# Access_System_Bmduino_V1_1.net
KiCad netlist of a schematic drawn in Altium Designer
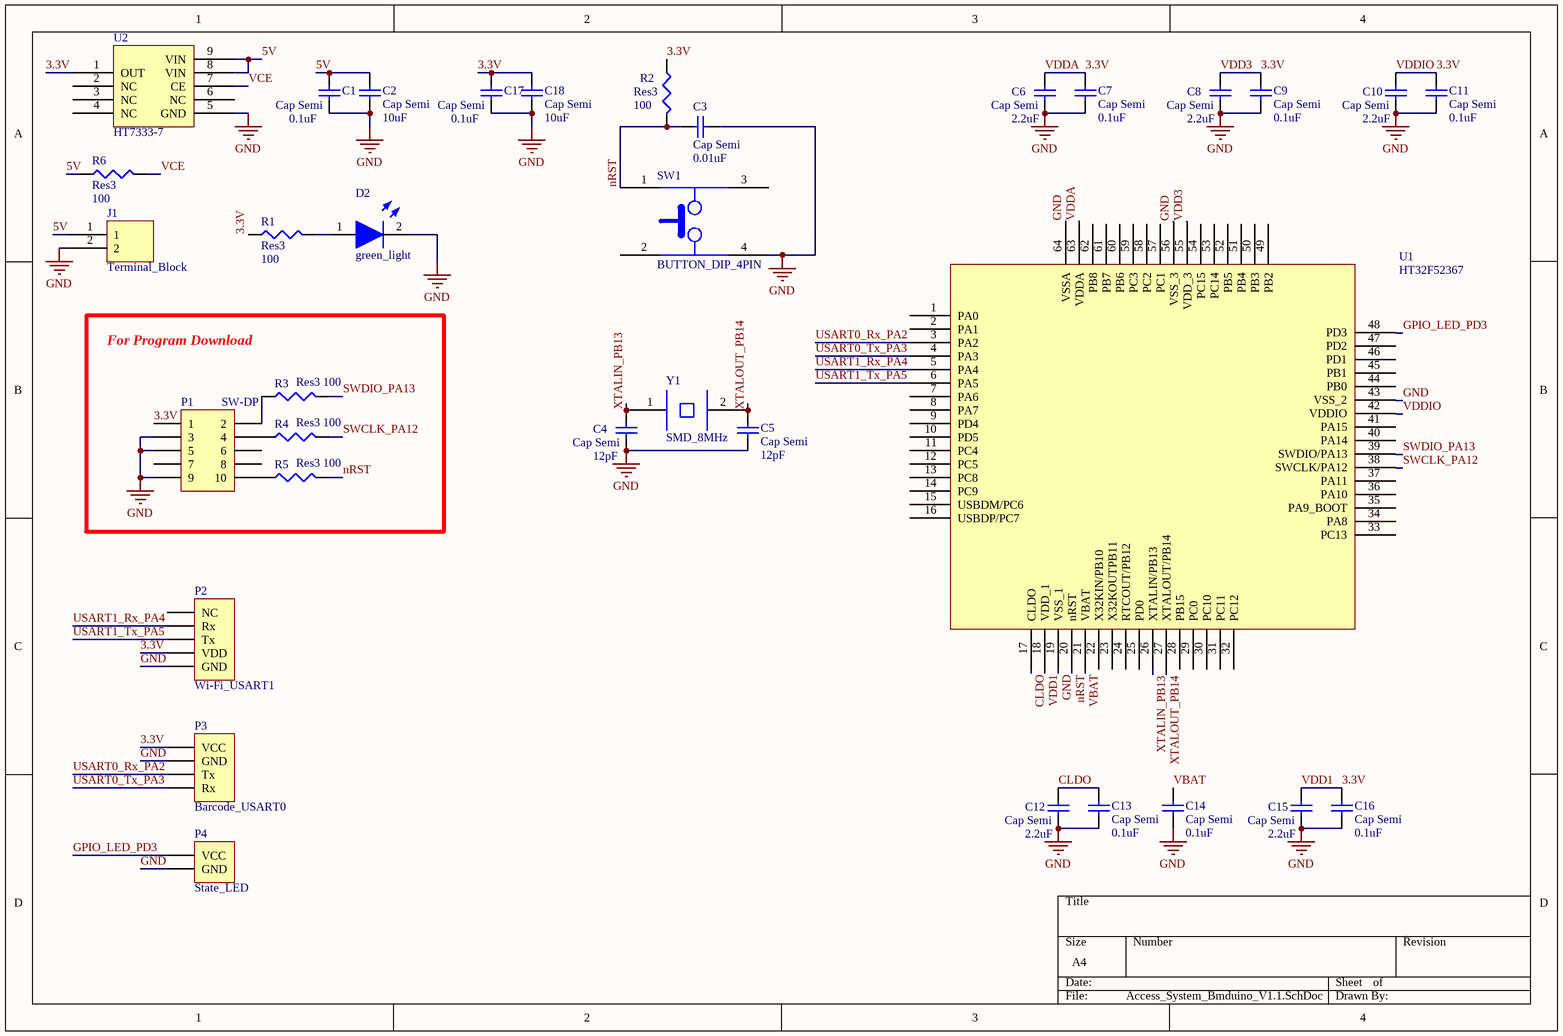
[diagram p0: Access_System_Bmduino_V1.1.SchDoc]

(export (version "E")
  (design (tool "Eeschema 10.0.6"))
  (components
    (comp (ref "C1")
      (value "Cap Semi")
      (footprint "1608[0603]")
      (description "Capacitor (Semiconductor SIM Model)")
      (fields (field (name "ALTIUM_VALUE") "0.1uF") (field (name "PUBLISHER") "Altium Limited"))
      (libsource (lib "Miscellaneous Devices") (part "Cap Semi"))
    )
    (comp (ref "C2")
      (value "Cap Semi")
      (footprint "1608[0603]")
      (description "Capacitor (Semiconductor SIM Model)")
      (fields (field (name "ALTIUM_VALUE") "10uF") (field (name "PUBLISHER") "Altium Limited"))
      (libsource (lib "Miscellaneous Devices") (part "Cap Semi"))
    )
    (comp (ref "C3")
      (value "Cap Semi")
      (footprint "1608[0603]")
      (description "Capacitor (Semiconductor SIM Model)")
      (fields (field (name "ALTIUM_VALUE") "0.01uF") (field (name "PUBLISHER") "Altium Limited"))
      (libsource (lib "Miscellaneous Devices") (part "Cap Semi"))
    )
    (comp (ref "C4")
      (value "Cap Semi")
      (footprint "1608[0603]")
      (description "Capacitor (Semiconductor SIM Model)")
      (fields (field (name "ALTIUM_VALUE") "12pF") (field (name "PUBLISHER") "Altium Limited"))
      (libsource (lib "Miscellaneous Devices") (part "Cap Semi"))
    )
    (comp (ref "C5")
      (value "Cap Semi")
      (footprint "1608[0603]")
      (description "Capacitor (Semiconductor SIM Model)")
      (fields (field (name "ALTIUM_VALUE") "12pF") (field (name "PUBLISHER") "Altium Limited"))
      (libsource (lib "Miscellaneous Devices") (part "Cap Semi"))
    )
    (comp (ref "C6")
      (value "Cap Semi")
      (footprint "1608[0603]")
      (description "Capacitor (Semiconductor SIM Model)")
      (fields (field (name "ALTIUM_VALUE") "2.2uF") (field (name "PUBLISHER") "Altium Limited"))
      (libsource (lib "Miscellaneous Devices") (part "Cap Semi"))
    )
    (comp (ref "C7")
      (value "Cap Semi")
      (footprint "1608[0603]")
      (description "Capacitor (Semiconductor SIM Model)")
      (fields (field (name "ALTIUM_VALUE") "0.1uF") (field (name "PUBLISHER") "Altium Limited"))
      (libsource (lib "Miscellaneous Devices") (part "Cap Semi"))
    )
    (comp (ref "C8")
      (value "Cap Semi")
      (footprint "1608[0603]")
      (description "Capacitor (Semiconductor SIM Model)")
      (fields (field (name "ALTIUM_VALUE") "2.2uF") (field (name "PUBLISHER") "Altium Limited"))
      (libsource (lib "Miscellaneous Devices") (part "Cap Semi"))
    )
    (comp (ref "C9")
      (value "Cap Semi")
      (footprint "1608[0603]")
      (description "Capacitor (Semiconductor SIM Model)")
      (fields (field (name "ALTIUM_VALUE") "0.1uF") (field (name "PUBLISHER") "Altium Limited"))
      (libsource (lib "Miscellaneous Devices") (part "Cap Semi"))
    )
    (comp (ref "C10")
      (value "Cap Semi")
      (footprint "1608[0603]")
      (description "Capacitor (Semiconductor SIM Model)")
      (fields (field (name "ALTIUM_VALUE") "2.2uF") (field (name "PUBLISHER") "Altium Limited"))
      (libsource (lib "Miscellaneous Devices") (part "Cap Semi"))
    )
    (comp (ref "C11")
      (value "Cap Semi")
      (footprint "1608[0603]")
      (description "Capacitor (Semiconductor SIM Model)")
      (fields (field (name "ALTIUM_VALUE") "0.1uF") (field (name "PUBLISHER") "Altium Limited"))
      (libsource (lib "Miscellaneous Devices") (part "Cap Semi"))
    )
    (comp (ref "C12")
      (value "Cap Semi")
      (footprint "1608[0603]")
      (description "Capacitor (Semiconductor SIM Model)")
      (fields (field (name "ALTIUM_VALUE") "2.2uF") (field (name "PUBLISHER") "Altium Limited"))
      (libsource (lib "Miscellaneous Devices") (part "Cap Semi"))
    )
    (comp (ref "C13")
      (value "Cap Semi")
      (footprint "1608[0603]")
      (description "Capacitor (Semiconductor SIM Model)")
      (fields (field (name "ALTIUM_VALUE") "0.1uF") (field (name "PUBLISHER") "Altium Limited"))
      (libsource (lib "Miscellaneous Devices") (part "Cap Semi"))
    )
    (comp (ref "C14")
      (value "Cap Semi")
      (footprint "1608[0603]")
      (description "Capacitor (Semiconductor SIM Model)")
      (fields (field (name "ALTIUM_VALUE") "0.1uF") (field (name "PUBLISHER") "Altium Limited"))
      (libsource (lib "Miscellaneous Devices") (part "Cap Semi"))
    )
    (comp (ref "C15")
      (value "Cap Semi")
      (footprint "1608[0603]")
      (description "Capacitor (Semiconductor SIM Model)")
      (fields (field (name "ALTIUM_VALUE") "2.2uF") (field (name "PUBLISHER") "Altium Limited"))
      (libsource (lib "Miscellaneous Devices") (part "Cap Semi"))
    )
    (comp (ref "C16")
      (value "Cap Semi")
      (footprint "1608[0603]")
      (description "Capacitor (Semiconductor SIM Model)")
      (fields (field (name "ALTIUM_VALUE") "0.1uF") (field (name "PUBLISHER") "Altium Limited"))
      (libsource (lib "Miscellaneous Devices") (part "Cap Semi"))
    )
    (comp (ref "C17")
      (value "Cap Semi")
      (footprint "1608[0603]")
      (description "Capacitor (Semiconductor SIM Model)")
      (fields (field (name "ALTIUM_VALUE") "0.1uF") (field (name "PUBLISHER") "Altium Limited"))
      (libsource (lib "Miscellaneous Devices") (part "Cap Semi"))
    )
    (comp (ref "C18")
      (value "Cap Semi")
      (footprint "1608[0603]")
      (description "Capacitor (Semiconductor SIM Model)")
      (fields (field (name "ALTIUM_VALUE") "10uF") (field (name "PUBLISHER") "Altium Limited"))
      (libsource (lib "Miscellaneous Devices") (part "Cap Semi"))
    )
    (comp (ref "D2")
      (value "green_light")
      (footprint "LED_Green")
      (libsource (lib "Lab_share") (part "LED_Green"))
    )
    (comp (ref "J1")
      (value "Terminal_Block")
      (footprint "terminal block")
      (libsource (lib "Lab_share") (part "Terminal Block"))
    )
    (comp (ref "P1")
      (value "SW-DP")
      (footprint "HDR2X5")
      (description "Header, 5-Pin, Dual row")
      (fields (field (name "PUBLISHER") "Altium Limited"))
      (libsource (lib "Miscellaneous Connectors") (part "Header 5X2"))
    )
    (comp (ref "P2")
      (value "Wi-Fi_USART1")
      (footprint "HDR1X5")
      (description "Header, 5-Pin")
      (fields (field (name "PUBLISHER") "Altium Limited"))
      (libsource (lib "Miscellaneous Connectors") (part "Header 5"))
    )
    (comp (ref "P3")
      (value "Barcode_USART0")
      (footprint "HDR1X4")
      (description "Header, 4-Pin")
      (fields (field (name "PUBLISHER") "Altium Limited"))
      (libsource (lib "Miscellaneous Connectors") (part "Header 4"))
    )
    (comp (ref "P4")
      (value "State_LED")
      (footprint "HDR1X2")
      (description "Header, 2-Pin")
      (fields (field (name "PUBLISHER") "Altium Limited"))
      (libsource (lib "Miscellaneous Connectors") (part "Header 2"))
    )
    (comp (ref "R1")
      (value "Res3")
      (footprint "J1-0603")
      (description "Resistor")
      (fields (field (name "ALTIUM_VALUE") "100") (field (name "PUBLISHER") "Altium Limited"))
      (libsource (lib "Miscellaneous Devices") (part "Res3"))
    )
    (comp (ref "R2")
      (value "Res3")
      (footprint "J1-0603")
      (description "Resistor")
      (fields (field (name "ALTIUM_VALUE") "100") (field (name "PUBLISHER") "Altium Limited"))
      (libsource (lib "Miscellaneous Devices") (part "Res3"))
    )
    (comp (ref "R3")
      (value "Res3")
      (footprint "J1-0603")
      (description "Resistor")
      (fields (field (name "ALTIUM_VALUE") "100") (field (name "PUBLISHER") "Altium Limited"))
      (libsource (lib "Miscellaneous Devices") (part "Res3"))
    )
    (comp (ref "R4")
      (value "Res3")
      (footprint "J1-0603")
      (description "Resistor")
      (fields (field (name "ALTIUM_VALUE") "100") (field (name "PUBLISHER") "Altium Limited"))
      (libsource (lib "Miscellaneous Devices") (part "Res3"))
    )
    (comp (ref "R5")
      (value "Res3")
      (footprint "J1-0603")
      (description "Resistor")
      (fields (field (name "ALTIUM_VALUE") "100") (field (name "PUBLISHER") "Altium Limited"))
      (libsource (lib "Miscellaneous Devices") (part "Res3"))
    )
    (comp (ref "R6")
      (value "Res3")
      (footprint "J1-0603")
      (description "Resistor")
      (fields (field (name "ALTIUM_VALUE") "100") (field (name "PUBLISHER") "Altium Limited"))
      (libsource (lib "Miscellaneous Devices") (part "Res3"))
    )
    (comp (ref "SW1")
      (value "BUTTON_DIP_4PIN")
      (footprint "Push_Button")
      (libsource (lib "Lab_share") (part "Push_Button"))
    )
    (comp (ref "U1")
      (value "HT32F52367")
      (footprint "HT32H52367")
      (libsource (lib "Lab_share") (part "HT32F52367"))
    )
    (comp (ref "U2") (value "HT7333-7") (footprint "HT7333") (libsource (lib "Lab_share") (part "HT7333")))
    (comp (ref "Y1")
      (value "SMD_8MHz")
      (footprint "Quartz-Crystal-8MHz")
      (libsource (lib "Lab_share") (part "Quartz_Crystal_8MHz"))
    )
  )
  (nets
    (net (code "1") (name "/3.3V") (class "Default")
      (node (ref "C10") (pin "1") (pinfunction "1_1") (pintype "passive"))
      (node (ref "C11") (pin "2") (pinfunction "2_2") (pintype "passive"))
      (node (ref "C15") (pin "1") (pinfunction "1_1") (pintype "passive"))
      (node (ref "C16") (pin "2") (pinfunction "2_2") (pintype "passive"))
      (node (ref "C17") (pin "2") (pinfunction "2_2") (pintype "passive"))
      (node (ref "C18") (pin "2") (pinfunction "2_2") (pintype "passive"))
      (node (ref "C6") (pin "1") (pinfunction "1_1") (pintype "passive"))
      (node (ref "C7") (pin "2") (pinfunction "2_2") (pintype "passive"))
      (node (ref "C8") (pin "1") (pinfunction "1_1") (pintype "passive"))
      (node (ref "C9") (pin "2") (pinfunction "2_2") (pintype "passive"))
      (node (ref "P1") (pin "1") (pinfunction "1_1") (pintype "passive"))
      (node (ref "P2") (pin "4") (pinfunction "VDD_4") (pintype "passive"))
      (node (ref "P3") (pin "1") (pinfunction "VCC_1") (pintype "passive"))
      (node (ref "R1") (pin "1") (pinfunction "1_1") (pintype "passive"))
      (node (ref "R2") (pin "1") (pinfunction "1_1") (pintype "passive"))
      (node (ref "U1") (pin "18") (pinfunction "VDD_1_18") (pintype "passive"))
      (node (ref "U1") (pin "42") (pinfunction "VDDIO_42") (pintype "passive"))
      (node (ref "U1") (pin "55") (pinfunction "VDD_3_55") (pintype "passive"))
      (node (ref "U1") (pin "63") (pinfunction "VDDA_63") (pintype "passive"))
      (node (ref "U2") (pin "1") (pinfunction "OUT_1") (pintype "passive"))
    )
    (net (code "2") (name "/5V") (class "Default")
      (node (ref "C1") (pin "2") (pinfunction "2_2") (pintype "passive"))
      (node (ref "C2") (pin "2") (pinfunction "2_2") (pintype "passive"))
      (node (ref "J1") (pin "1") (pinfunction "1_1") (pintype "passive"))
      (node (ref "R6") (pin "1") (pinfunction "1_1") (pintype "passive"))
      (node (ref "U2") (pin "8") (pinfunction "VIN_8") (pintype "passive"))
      (node (ref "U2") (pin "9") (pinfunction "VIN_9") (pintype "passive"))
    )
    (net (code "3") (name "/CLDO") (class "Default")
      (node (ref "C12") (pin "1") (pinfunction "1_1") (pintype "passive"))
      (node (ref "C13") (pin "2") (pinfunction "2_2") (pintype "passive"))
      (node (ref "U1") (pin "17") (pinfunction "CLDO_17") (pintype "passive"))
    )
    (net (code "4") (name "/GPIO_LED_PD3") (class "Default")
      (node (ref "P4") (pin "1") (pinfunction "VCC_1") (pintype "passive"))
      (node (ref "U1") (pin "48") (pinfunction "PD3_48") (pintype "passive"))
    )
    (net (code "5") (name "/SWCLK_PA12") (class "Default")
      (node (ref "R4") (pin "2") (pinfunction "2_2") (pintype "passive"))
      (node (ref "U1") (pin "38") (pinfunction "SWCLK/PA12_38") (pintype "passive"))
    )
    (net (code "6") (name "/SWDIO_PA13") (class "Default")
      (node (ref "R3") (pin "2") (pinfunction "2_2") (pintype "passive"))
      (node (ref "U1") (pin "39") (pinfunction "SWDIO/PA13_39") (pintype "passive"))
    )
    (net (code "7") (name "/USART0_Rx_PA2") (class "Default")
      (node (ref "P3") (pin "3") (pinfunction "Tx_3") (pintype "passive"))
      (node (ref "U1") (pin "3") (pinfunction "PA2_3") (pintype "passive"))
    )
    (net (code "8") (name "/USART0_Tx_PA3") (class "Default")
      (node (ref "P3") (pin "4") (pinfunction "Rx_4") (pintype "passive"))
      (node (ref "U1") (pin "4") (pinfunction "PA3_4") (pintype "passive"))
    )
    (net (code "9") (name "/USART1_Rx_PA4") (class "Default")
      (node (ref "P2") (pin "2") (pinfunction "Rx_2") (pintype "passive"))
      (node (ref "U1") (pin "5") (pinfunction "PA4_5") (pintype "passive"))
    )
    (net (code "10") (name "/USART1_Tx_PA5") (class "Default")
      (node (ref "P2") (pin "3") (pinfunction "Tx_3") (pintype "passive"))
      (node (ref "U1") (pin "6") (pinfunction "PA5_6") (pintype "passive"))
    )
    (net (code "11") (name "/VBAT") (class "Default")
      (node (ref "C14") (pin "2") (pinfunction "2_2") (pintype "passive"))
      (node (ref "U1") (pin "21") (pinfunction "VBAT_21") (pintype "passive"))
    )
    (net (code "12") (name "/VCE") (class "Default")
      (node (ref "R6") (pin "2") (pinfunction "2_2") (pintype "passive"))
      (node (ref "U2") (pin "7") (pinfunction "CE_7") (pintype "passive"))
    )
    (net (code "13") (name "/XTALIN_PB13") (class "Default")
      (node (ref "C4") (pin "1") (pinfunction "1_1") (pintype "passive"))
      (node (ref "U1") (pin "26") (pinfunction "XTALIN/PB13_26") (pintype "passive"))
      (node (ref "Y1") (pin "1") (pintype "passive"))
    )
    (net (code "14") (name "/XTALOUT_PB14") (class "Default")
      (node (ref "C5") (pin "2") (pinfunction "2_2") (pintype "passive"))
      (node (ref "U1") (pin "27") (pinfunction "XTALOUT/PB14_27") (pintype "passive"))
      (node (ref "Y1") (pin "2") (pintype "passive"))
    )
    (net (code "15") (name "/nRST") (class "Default")
      (node (ref "C3") (pin "2") (pinfunction "2_2") (pintype "passive"))
      (node (ref "R2") (pin "2") (pinfunction "2_2") (pintype "passive"))
      (node (ref "R5") (pin "2") (pinfunction "2_2") (pintype "passive"))
      (node (ref "SW1") (pin "1") (pintype "passive"))
      (node (ref "U1") (pin "20") (pinfunction "nRST_20") (pintype "passive"))
    )
    (net (code "16") (name "GND") (class "Default")
      (node (ref "C1") (pin "1") (pinfunction "1_1") (pintype "passive"))
      (node (ref "C10") (pin "2") (pinfunction "2_2") (pintype "passive"))
      (node (ref "C11") (pin "1") (pinfunction "1_1") (pintype "passive"))
      (node (ref "C12") (pin "2") (pinfunction "2_2") (pintype "passive"))
      (node (ref "C13") (pin "1") (pinfunction "1_1") (pintype "passive"))
      (node (ref "C14") (pin "1") (pinfunction "1_1") (pintype "passive"))
      (node (ref "C15") (pin "2") (pinfunction "2_2") (pintype "passive"))
      (node (ref "C16") (pin "1") (pinfunction "1_1") (pintype "passive"))
      (node (ref "C17") (pin "1") (pinfunction "1_1") (pintype "passive"))
      (node (ref "C18") (pin "1") (pinfunction "1_1") (pintype "passive"))
      (node (ref "C2") (pin "1") (pinfunction "1_1") (pintype "passive"))
      (node (ref "C3") (pin "1") (pinfunction "1_1") (pintype "passive"))
      (node (ref "C4") (pin "2") (pinfunction "2_2") (pintype "passive"))
      (node (ref "C5") (pin "1") (pinfunction "1_1") (pintype "passive"))
      (node (ref "C6") (pin "2") (pinfunction "2_2") (pintype "passive"))
      (node (ref "C7") (pin "1") (pinfunction "1_1") (pintype "passive"))
      (node (ref "C8") (pin "2") (pinfunction "2_2") (pintype "passive"))
      (node (ref "C9") (pin "1") (pinfunction "1_1") (pintype "passive"))
      (node (ref "D2") (pin "2") (pintype "passive"))
      (node (ref "J1") (pin "2") (pinfunction "2_2") (pintype "passive"))
      (node (ref "P1") (pin "3") (pinfunction "3_3") (pintype "passive"))
      (node (ref "P1") (pin "5") (pinfunction "5_5") (pintype "passive"))
      (node (ref "P1") (pin "9") (pinfunction "9_9") (pintype "passive"))
      (node (ref "P2") (pin "5") (pinfunction "GND_5") (pintype "passive"))
      (node (ref "P3") (pin "2") (pinfunction "GND_2") (pintype "passive"))
      (node (ref "P4") (pin "2") (pinfunction "GND_2") (pintype "passive"))
      (node (ref "SW1") (pin "4") (pintype "passive"))
      (node (ref "U1") (pin "19") (pinfunction "VSS_1_19") (pintype "passive"))
      (node (ref "U1") (pin "43") (pinfunction "VSS_2_43") (pintype "passive"))
      (node (ref "U1") (pin "56") (pinfunction "VSS_3_56") (pintype "passive"))
      (node (ref "U1") (pin "64") (pinfunction "VSSA_64") (pintype "passive"))
      (node (ref "U2") (pin "5") (pinfunction "GND_5") (pintype "passive"))
    )
    (net (code "17") (name "Net-(D2-Pad1)") (class "Default")
      (node (ref "D2") (pin "1") (pintype "passive"))
      (node (ref "R1") (pin "2") (pinfunction "2_2") (pintype "passive"))
    )
    (net (code "18") (name "Net-(P1-Pad2)") (class "Default")
      (node (ref "P1") (pin "2") (pinfunction "2_2") (pintype "passive"))
      (node (ref "R3") (pin "1") (pinfunction "1_1") (pintype "passive"))
    )
    (net (code "19") (name "Net-(P1-Pad4)") (class "Default")
      (node (ref "P1") (pin "4") (pinfunction "4_4") (pintype "passive"))
      (node (ref "R4") (pin "1") (pinfunction "1_1") (pintype "passive"))
    )
    (net (code "20") (name "Net-(P1-Pad10)") (class "Default")
      (node (ref "P1") (pin "10") (pinfunction "10_10") (pintype "passive"))
      (node (ref "R5") (pin "1") (pinfunction "1_1") (pintype "passive"))
    )
    (net (code "21") (name "unconnected-(P1-Pad6)") (class "Default")
      (node (ref "P1") (pin "6") (pinfunction "6_6") (pintype "passive"))
    )
    (net (code "22") (name "unconnected-(P1-Pad7)") (class "Default")
      (node (ref "P1") (pin "7") (pinfunction "7_7") (pintype "passive"))
    )
    (net (code "23") (name "unconnected-(P1-Pad8)") (class "Default")
      (node (ref "P1") (pin "8") (pinfunction "8_8") (pintype "passive"))
    )
    (net (code "24") (name "unconnected-(P2-NC-Pad1)") (class "Default")
      (node (ref "P2") (pin "1") (pinfunction "NC_1") (pintype "passive"))
    )
    (net (code "25") (name "unconnected-(SW1-Pad2)") (class "Default")
      (node (ref "SW1") (pin "2") (pintype "passive"))
    )
    (net (code "26") (name "unconnected-(SW1-Pad3)") (class "Default")
      (node (ref "SW1") (pin "3") (pintype "passive"))
    )
    (net (code "27") (name "unconnected-(U1-PA0-Pad1)") (class "Default")
      (node (ref "U1") (pin "1") (pinfunction "PA0_1") (pintype "passive"))
    )
    (net (code "28") (name "unconnected-(U1-PA1-Pad2)") (class "Default")
      (node (ref "U1") (pin "2") (pinfunction "PA1_2") (pintype "passive"))
    )
    (net (code "29") (name "unconnected-(U1-PA6-Pad7)") (class "Default")
      (node (ref "U1") (pin "7") (pinfunction "PA6_7") (pintype "passive"))
    )
    (net (code "30") (name "unconnected-(U1-PA7-Pad8)") (class "Default")
      (node (ref "U1") (pin "8") (pinfunction "PA7_8") (pintype "passive"))
    )
    (net (code "31") (name "unconnected-(U1-PA8-Pad34)") (class "Default")
      (node (ref "U1") (pin "34") (pinfunction "PA8_34") (pintype "passive"))
    )
    (net (code "32") (name "unconnected-(U1-PA9_BOOT-Pad35)") (class "Default")
      (node (ref "U1") (pin "35") (pinfunction "PA9_BOOT_35") (pintype "passive"))
    )
    (net (code "33") (name "unconnected-(U1-PA10-Pad36)") (class "Default")
      (node (ref "U1") (pin "36") (pinfunction "PA10_36") (pintype "passive"))
    )
    (net (code "34") (name "unconnected-(U1-PA11-Pad37)") (class "Default")
      (node (ref "U1") (pin "37") (pinfunction "PA11_37") (pintype "passive"))
    )
    (net (code "35") (name "unconnected-(U1-PA14-Pad40)") (class "Default")
      (node (ref "U1") (pin "40") (pinfunction "PA14_40") (pintype "passive"))
    )
    (net (code "36") (name "unconnected-(U1-PA15-Pad41)") (class "Default")
      (node (ref "U1") (pin "41") (pinfunction "PA15_41") (pintype "passive"))
    )
    (net (code "37") (name "unconnected-(U1-PB0-Pad44)") (class "Default")
      (node (ref "U1") (pin "44") (pinfunction "PB0_44") (pintype "passive"))
    )
    (net (code "38") (name "unconnected-(U1-PB1-Pad45)") (class "Default")
      (node (ref "U1") (pin "45") (pinfunction "PB1_45") (pintype "passive"))
    )
    (net (code "39") (name "unconnected-(U1-PB2-Pad49)") (class "Default")
      (node (ref "U1") (pin "49") (pinfunction "PB2_49") (pintype "passive"))
    )
    (net (code "40") (name "unconnected-(U1-PB3-Pad50)") (class "Default")
      (node (ref "U1") (pin "50") (pinfunction "PB3_50") (pintype "passive"))
    )
    (net (code "41") (name "unconnected-(U1-PB4-Pad51)") (class "Default")
      (node (ref "U1") (pin "51") (pinfunction "PB4_51") (pintype "passive"))
    )
    (net (code "42") (name "unconnected-(U1-PB5-Pad52)") (class "Default")
      (node (ref "U1") (pin "52") (pinfunction "PB5_52") (pintype "passive"))
    )
    (net (code "43") (name "unconnected-(U1-PB6-Pad60)") (class "Default")
      (node (ref "U1") (pin "60") (pinfunction "PB6_60") (pintype "passive"))
    )
    (net (code "44") (name "unconnected-(U1-PB7-Pad61)") (class "Default")
      (node (ref "U1") (pin "61") (pinfunction "PB7_61") (pintype "passive"))
    )
    (net (code "45") (name "unconnected-(U1-PB8-Pad62)") (class "Default")
      (node (ref "U1") (pin "62") (pinfunction "PB8_62") (pintype "passive"))
    )
    (net (code "46") (name "unconnected-(U1-PB15-Pad28)") (class "Default")
      (node (ref "U1") (pin "28") (pinfunction "PB15_28") (pintype "passive"))
    )
    (net (code "47") (name "unconnected-(U1-PC0-Pad29)") (class "Default")
      (node (ref "U1") (pin "29") (pinfunction "PC0_29") (pintype "passive"))
    )
    (net (code "48") (name "unconnected-(U1-PC1-Pad57)") (class "Default")
      (node (ref "U1") (pin "57") (pinfunction "PC1_57") (pintype "passive"))
    )
    (net (code "49") (name "unconnected-(U1-PC2-Pad58)") (class "Default")
      (node (ref "U1") (pin "58") (pinfunction "PC2_58") (pintype "passive"))
    )
    (net (code "50") (name "unconnected-(U1-PC3-Pad59)") (class "Default")
      (node (ref "U1") (pin "59") (pinfunction "PC3_59") (pintype "passive"))
    )
    (net (code "51") (name "unconnected-(U1-PC4-Pad11)") (class "Default")
      (node (ref "U1") (pin "11") (pinfunction "PC4_11") (pintype "passive"))
    )
    (net (code "52") (name "unconnected-(U1-PC5-Pad12)") (class "Default")
      (node (ref "U1") (pin "12") (pinfunction "PC5_12") (pintype "passive"))
    )
    (net (code "53") (name "unconnected-(U1-PC8-Pad13)") (class "Default")
      (node (ref "U1") (pin "13") (pinfunction "PC8_13") (pintype "passive"))
    )
    (net (code "54") (name "unconnected-(U1-PC9-Pad14)") (class "Default")
      (node (ref "U1") (pin "14") (pinfunction "PC9_14") (pintype "passive"))
    )
    (net (code "55") (name "unconnected-(U1-PC10-Pad30)") (class "Default")
      (node (ref "U1") (pin "30") (pinfunction "PC10_30") (pintype "passive"))
    )
    (net (code "56") (name "unconnected-(U1-PC11-Pad31)") (class "Default")
      (node (ref "U1") (pin "31") (pinfunction "PC11_31") (pintype "passive"))
    )
    (net (code "57") (name "unconnected-(U1-PC12-Pad32)") (class "Default")
      (node (ref "U1") (pin "32") (pinfunction "PC12_32") (pintype "passive"))
    )
    (net (code "58") (name "unconnected-(U1-PC13-Pad33)") (class "Default")
      (node (ref "U1") (pin "33") (pinfunction "PC13_33") (pintype "passive"))
    )
    (net (code "59") (name "unconnected-(U1-PC14-Pad53)") (class "Default")
      (node (ref "U1") (pin "53") (pinfunction "PC14_53") (pintype "passive"))
    )
    (net (code "60") (name "unconnected-(U1-PC15-Pad54)") (class "Default")
      (node (ref "U1") (pin "54") (pinfunction "PC15_54") (pintype "passive"))
    )
    (net (code "61") (name "unconnected-(U1-PD0-Pad25)") (class "Default")
      (node (ref "U1") (pin "25") (pinfunction "PD0_25") (pintype "passive"))
    )
    (net (code "62") (name "unconnected-(U1-PD1-Pad46)") (class "Default")
      (node (ref "U1") (pin "46") (pinfunction "PD1_46") (pintype "passive"))
    )
    (net (code "63") (name "unconnected-(U1-PD2-Pad47)") (class "Default")
      (node (ref "U1") (pin "47") (pinfunction "PD2_47") (pintype "passive"))
    )
    (net (code "64") (name "unconnected-(U1-PD4-Pad9)") (class "Default")
      (node (ref "U1") (pin "9") (pinfunction "PD4_9") (pintype "passive"))
    )
    (net (code "65") (name "unconnected-(U1-PD5-Pad10)") (class "Default")
      (node (ref "U1") (pin "10") (pinfunction "PD5_10") (pintype "passive"))
    )
    (net (code "66") (name "unconnected-(U1-RTCOUT{slash}PB12-Pad24)") (class "Default")
      (node (ref "U1") (pin "24") (pinfunction "RTCOUT/PB12_24") (pintype "passive"))
    )
    (net (code "67") (name "unconnected-(U1-USBDM{slash}PC6-Pad15)") (class "Default")
      (node (ref "U1") (pin "15") (pinfunction "USBDM/PC6_15") (pintype "passive"))
    )
    (net (code "68") (name "unconnected-(U1-USBDP{slash}PC7-Pad16)") (class "Default")
      (node (ref "U1") (pin "16") (pinfunction "USBDP/PC7_16") (pintype "passive"))
    )
    (net (code "69") (name "unconnected-(U1-X32KIN{slash}PB10-Pad22)") (class "Default")
      (node (ref "U1") (pin "22") (pinfunction "X32KIN/PB10_22") (pintype "passive"))
    )
    (net (code "70") (name "unconnected-(U1-X32KOUTPB11-Pad23)") (class "Default")
      (node (ref "U1") (pin "23") (pinfunction "X32KOUTPB11_23") (pintype "passive"))
    )
    (net (code "71") (name "unconnected-(U2-NC-Pad2)") (class "Default")
      (node (ref "U2") (pin "2") (pinfunction "NC_2") (pintype "passive"))
    )
    (net (code "72") (name "unconnected-(U2-NC-Pad3)") (class "Default")
      (node (ref "U2") (pin "3") (pinfunction "NC_3") (pintype "passive"))
    )
    (net (code "73") (name "unconnected-(U2-NC-Pad4)") (class "Default")
      (node (ref "U2") (pin "4") (pinfunction "NC_4") (pintype "passive"))
    )
    (net (code "74") (name "unconnected-(U2-NC-Pad6)") (class "Default")
      (node (ref "U2") (pin "6") (pinfunction "NC_6") (pintype "passive"))
    )
  )
)
